# 9xVoice_MikeB_NoRS232_SMD_v1_0d.net
KiCad netlist of a schematic drawn in EAGLE
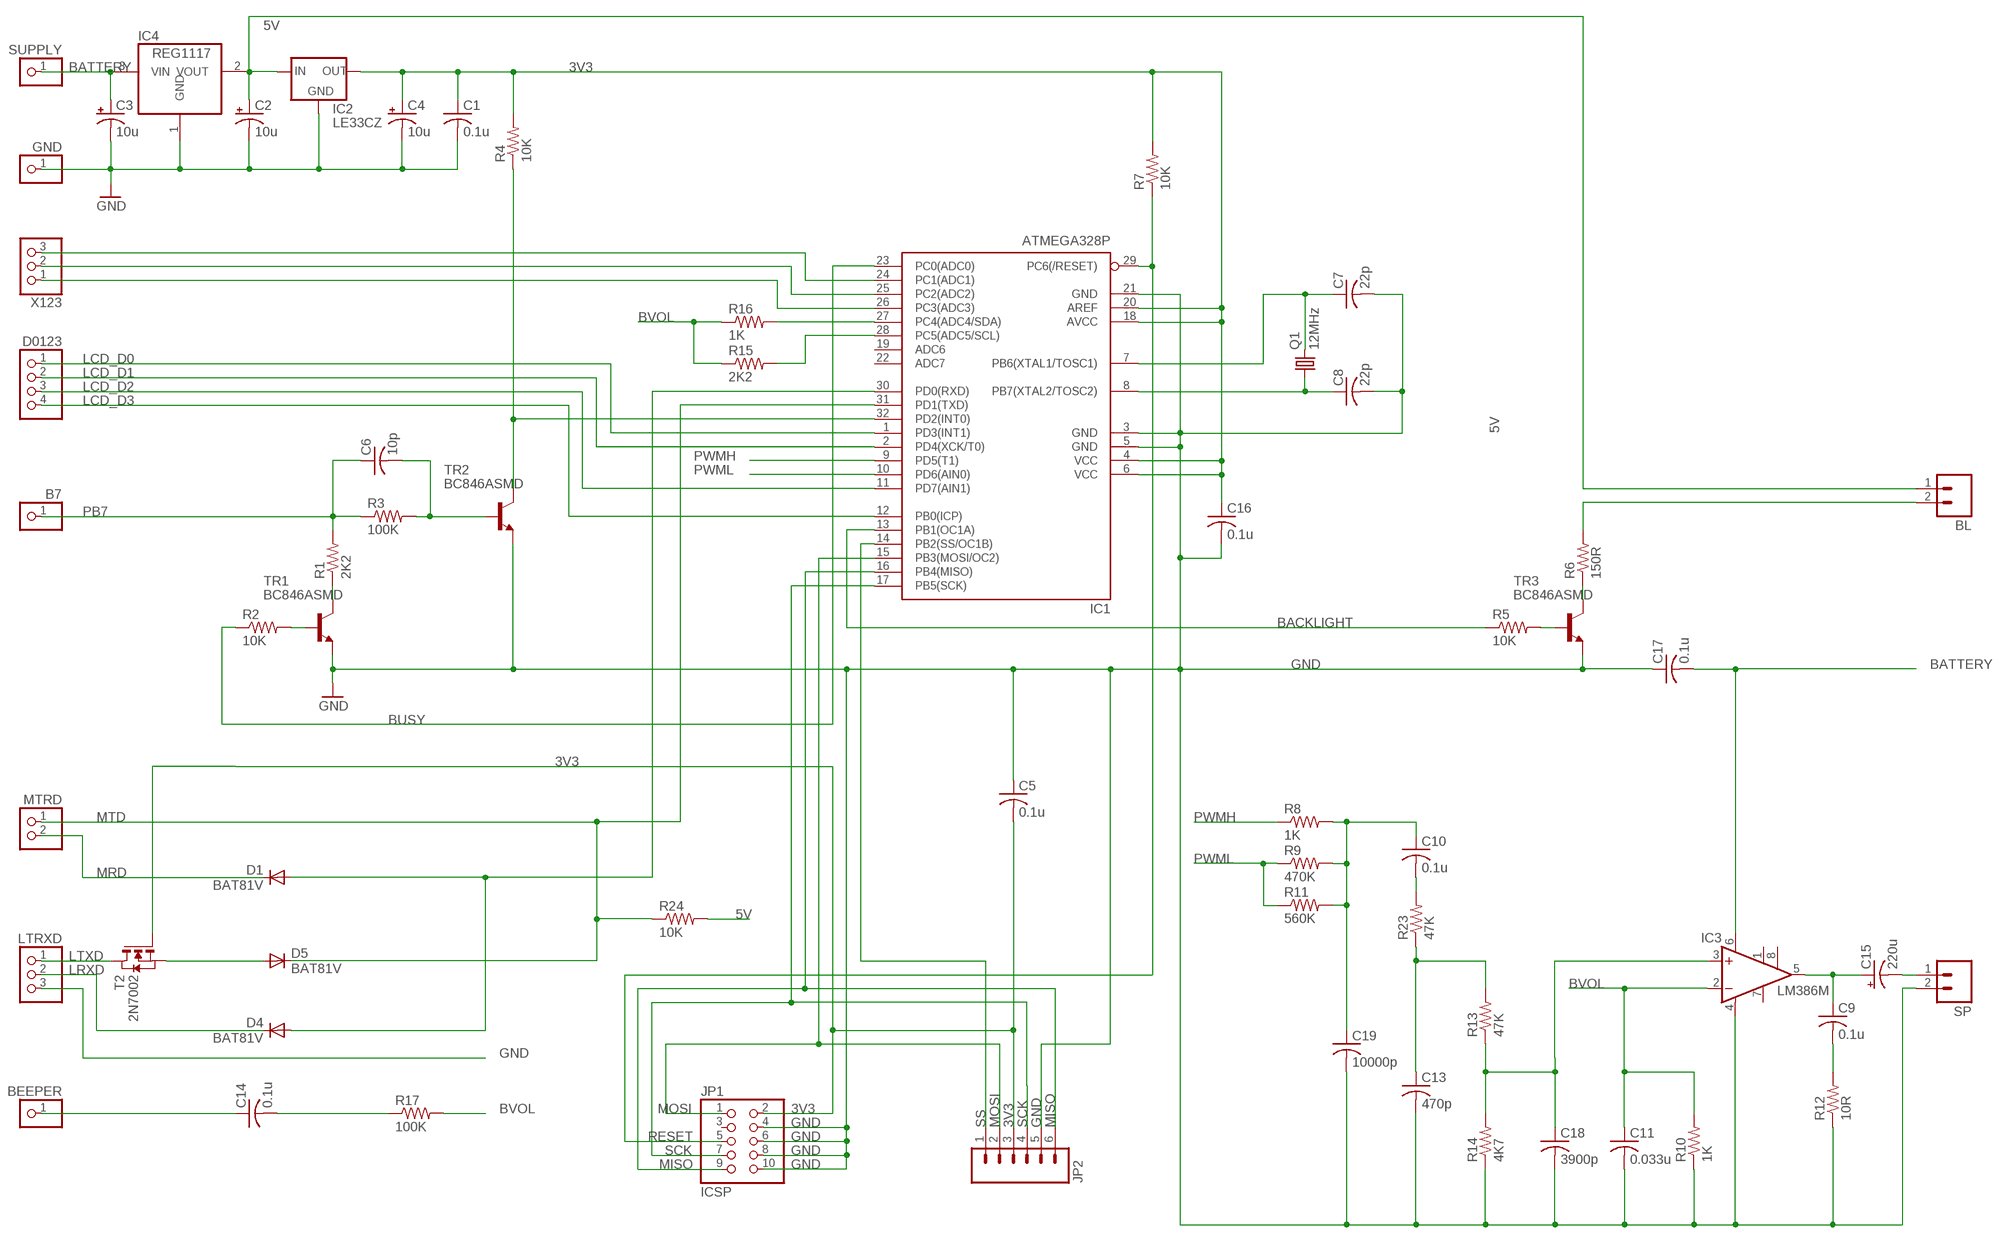
[diagram p0: schematic, sheet 1]

(export (version "E")
  (design (tool "Eeschema 10.0.6"))
  (components
    (comp (ref "B7")
      (value "PINHD-1X1")
      (footprint "eagle-import:1X01")
      (libsource (lib "eagle-import") (part "PINHD-1X1"))
    )
    (comp (ref "BEEPER")
      (value "PINHD-1X1")
      (footprint "eagle-import:1X01")
      (libsource (lib "eagle-import") (part "PINHD-1X1"))
    )
    (comp (ref "BL")
      (value "M02PTH")
      (footprint "eagle-import:1X02")
      (libsource (lib "eagle-import") (part "M02PTH"))
    )
    (comp (ref "C1")
      (value "0.1u")
      (footprint "eagle-import:C1206")
      (libsource (lib "eagle-import") (part "C-USC1206"))
    )
    (comp (ref "C2")
      (value "10u")
      (footprint "eagle-import:A_3216-18R")
      (libsource (lib "eagle-import") (part "CPOL-USA/3216-18R"))
    )
    (comp (ref "C3")
      (value "10u")
      (footprint "eagle-import:A_3216-18R")
      (libsource (lib "eagle-import") (part "CPOL-USA/3216-18R"))
    )
    (comp (ref "C4")
      (value "10u")
      (footprint "eagle-import:A_3216-18R")
      (libsource (lib "eagle-import") (part "CPOL-USA/3216-18R"))
    )
    (comp (ref "C5")
      (value "0.1u")
      (footprint "eagle-import:C1206")
      (libsource (lib "eagle-import") (part "C-USC1206"))
    )
    (comp (ref "C6")
      (value "10p")
      (footprint "eagle-import:C1206")
      (libsource (lib "eagle-import") (part "C-USC1206"))
    )
    (comp (ref "C7")
      (value "22p")
      (footprint "eagle-import:C1206")
      (libsource (lib "eagle-import") (part "C-USC1206"))
    )
    (comp (ref "C8")
      (value "22p")
      (footprint "eagle-import:C1206")
      (libsource (lib "eagle-import") (part "C-USC1206"))
    )
    (comp (ref "C9")
      (value "0.1u")
      (footprint "eagle-import:C1206")
      (libsource (lib "eagle-import") (part "C-USC1206"))
    )
    (comp (ref "C10")
      (value "0.1u")
      (footprint "eagle-import:C1206")
      (libsource (lib "eagle-import") (part "C-USC1206"))
    )
    (comp (ref "C11")
      (value "0.033u")
      (footprint "eagle-import:C1206")
      (libsource (lib "eagle-import") (part "C-USC1206"))
    )
    (comp (ref "C13")
      (value "470p")
      (footprint "eagle-import:C1206")
      (libsource (lib "eagle-import") (part "C-USC1206"))
    )
    (comp (ref "C14")
      (value "0.1u")
      (footprint "eagle-import:C1206")
      (libsource (lib "eagle-import") (part "C-USC1206"))
    )
    (comp (ref "C15")
      (value "220u")
      (footprint "eagle-import:CT7343")
      (libsource (lib "eagle-import") (part "CPOL-USCT7343"))
    )
    (comp (ref "C16")
      (value "0.1u")
      (footprint "eagle-import:C1206")
      (libsource (lib "eagle-import") (part "C-USC1206"))
    )
    (comp (ref "C17")
      (value "0.1u")
      (footprint "eagle-import:C1206")
      (libsource (lib "eagle-import") (part "C-USC1206"))
    )
    (comp (ref "C18")
      (value "3900p")
      (footprint "eagle-import:C1206")
      (libsource (lib "eagle-import") (part "C-USC1206"))
    )
    (comp (ref "C19")
      (value "10000p")
      (footprint "eagle-import:C1206")
      (libsource (lib "eagle-import") (part "C-USC1206"))
    )
    (comp (ref "D1")
      (value "BAT81V")
      (footprint "eagle-import:SOD123")
      (libsource (lib "eagle-import") (part "DIODE-SOD123"))
    )
    (comp (ref "D4")
      (value "BAT81V")
      (footprint "eagle-import:SOD123")
      (libsource (lib "eagle-import") (part "DIODE-SOD123"))
    )
    (comp (ref "D5")
      (value "BAT81V")
      (footprint "eagle-import:SOD123")
      (libsource (lib "eagle-import") (part "DIODE-SOD123"))
    )
    (comp (ref "D0123")
      (value "PINHD-1X4")
      (footprint "eagle-import:1X04")
      (libsource (lib "eagle-import") (part "PINHD-1X4"))
    )
    (comp (ref "GND")
      (value "PINHD-1X1")
      (footprint "eagle-import:1X01")
      (libsource (lib "eagle-import") (part "PINHD-1X1"))
    )
    (comp (ref "IC1")
      (value "ATMEGA328P")
      (footprint "eagle-import:TQFP32-08")
      (fields
        (field (name "MPN") "ATMEGA8-16AU")
        (field (name "MPN_1") "ATMEGA8-16AU")
        (field (name "OC_FARNELL") "9171371")
        (field (name "OC_NEWARK") "73M8863")
      )
      (libsource (lib "eagle-import") (part "MEGA8-AI"))
    )
    (comp (ref "IC2")
      (value "LE33CZ")
      (footprint "eagle-import:SOT23")
      (libsource (lib "eagle-import") (part "XC63FPM"))
    )
    (comp (ref "IC3")
      (value "LM386M")
      (footprint "eagle-import:SO08")
      (libsource (lib "eagle-import") (part "LM386?-M1"))
    )
    (comp (ref "IC4")
      (value "REG1117")
      (footprint "eagle-import:SOT223")
      (libsource (lib "eagle-import") (part "REG1117"))
    )
    (comp (ref "JP1")
      (value "ICSP")
      (footprint "eagle-import:2X05")
      (libsource (lib "eagle-import") (part "PINHD-2X5"))
    )
    (comp (ref "JP2")
      (value "M06SIP")
      (footprint "eagle-import:1X06")
      (libsource (lib "eagle-import") (part "M06SIP"))
    )
    (comp (ref "LTRXD")
      (value "PINHD-1X3")
      (footprint "eagle-import:1X03")
      (libsource (lib "eagle-import") (part "PINHD-1X3"))
    )
    (comp (ref "MTRD")
      (value "PINHD-1X2")
      (footprint "eagle-import:1X02")
      (libsource (lib "eagle-import") (part "PINHD-1X2"))
    )
    (comp (ref "Q1")
      (value "12MHz")
      (footprint "eagle-import:2-SMD")
      (libsource (lib "eagle-import") (part "7A"))
    )
    (comp (ref "R1")
      (value "2K2")
      (footprint "eagle-import:R1206")
      (libsource (lib "eagle-import") (part "R-US_R1206"))
    )
    (comp (ref "R2")
      (value "10K")
      (footprint "eagle-import:R1206")
      (libsource (lib "eagle-import") (part "R-US_R1206"))
    )
    (comp (ref "R3")
      (value "100K")
      (footprint "eagle-import:R1206")
      (libsource (lib "eagle-import") (part "R-US_R1206"))
    )
    (comp (ref "R4")
      (value "10K")
      (footprint "eagle-import:R1206")
      (libsource (lib "eagle-import") (part "R-US_R1206"))
    )
    (comp (ref "R5")
      (value "10K")
      (footprint "eagle-import:R1206")
      (libsource (lib "eagle-import") (part "R-US_R1206"))
    )
    (comp (ref "R6")
      (value "150R")
      (footprint "eagle-import:R1206")
      (libsource (lib "eagle-import") (part "R-US_R1206"))
    )
    (comp (ref "R7")
      (value "10K")
      (footprint "eagle-import:R1206")
      (libsource (lib "eagle-import") (part "R-US_R1206"))
    )
    (comp (ref "R8")
      (value "1K")
      (footprint "eagle-import:R1206")
      (libsource (lib "eagle-import") (part "R-US_R1206"))
    )
    (comp (ref "R9")
      (value "470K")
      (footprint "eagle-import:R1206")
      (libsource (lib "eagle-import") (part "R-US_R1206"))
    )
    (comp (ref "R10")
      (value "1K")
      (footprint "eagle-import:R1206")
      (libsource (lib "eagle-import") (part "R-US_R1206"))
    )
    (comp (ref "R11")
      (value "560K")
      (footprint "eagle-import:R1206")
      (libsource (lib "eagle-import") (part "R-US_R1206"))
    )
    (comp (ref "R12")
      (value "10R")
      (footprint "eagle-import:R1206")
      (libsource (lib "eagle-import") (part "R-US_R1206"))
    )
    (comp (ref "R13")
      (value "47K")
      (footprint "eagle-import:R1206")
      (libsource (lib "eagle-import") (part "R-US_R1206"))
    )
    (comp (ref "R14")
      (value "4K7")
      (footprint "eagle-import:R1206")
      (libsource (lib "eagle-import") (part "R-US_R1206"))
    )
    (comp (ref "R15")
      (value "2K2")
      (footprint "eagle-import:R1206")
      (libsource (lib "eagle-import") (part "R-US_R1206"))
    )
    (comp (ref "R16")
      (value "1K")
      (footprint "eagle-import:R1206")
      (libsource (lib "eagle-import") (part "R-US_R1206"))
    )
    (comp (ref "R17")
      (value "100K")
      (footprint "eagle-import:R1206")
      (libsource (lib "eagle-import") (part "R-US_R1206"))
    )
    (comp (ref "R23")
      (value "47K")
      (footprint "eagle-import:R1206")
      (libsource (lib "eagle-import") (part "R-US_R1206"))
    )
    (comp (ref "R24")
      (value "10K")
      (footprint "eagle-import:R1206")
      (libsource (lib "eagle-import") (part "R-US_R1206"))
    )
    (comp (ref "SP")
      (value "M02PTH")
      (footprint "eagle-import:1X02")
      (libsource (lib "eagle-import") (part "M02PTH"))
    )
    (comp (ref "SUPPLY")
      (value "PINHD-1X1")
      (footprint "eagle-import:1X01")
      (libsource (lib "eagle-import") (part "PINHD-1X1"))
    )
    (comp (ref "T2")
      (value "2N7002")
      (footprint "eagle-import:SOT-23")
      (libsource (lib "eagle-import") (part "NMOSSOT23"))
    )
    (comp (ref "TR1")
      (value "BC846ASMD")
      (footprint "eagle-import:SOT23")
      (libsource (lib "eagle-import") (part "BC846SMDA"))
    )
    (comp (ref "TR2")
      (value "BC846ASMD")
      (footprint "eagle-import:SOT23")
      (libsource (lib "eagle-import") (part "BC846SMDA"))
    )
    (comp (ref "TR3")
      (value "BC846ASMD")
      (footprint "eagle-import:SOT23")
      (libsource (lib "eagle-import") (part "BC846SMDA"))
    )
    (comp (ref "X123")
      (value "PINHD-1X3")
      (footprint "eagle-import:1X03")
      (libsource (lib "eagle-import") (part "PINHD-1X3"))
    )
  )
  (nets
    (net (code "1") (name "/3V3") (class "Default")
      (node (ref "C1") (pin "1") (pinfunction "1_1") (pintype "passive"))
      (node (ref "C16") (pin "1") (pinfunction "1_1") (pintype "passive"))
      (node (ref "C4") (pin "+") (pinfunction "+_+") (pintype "passive"))
      (node (ref "C5") (pin "2") (pinfunction "2_2") (pintype "passive"))
      (node (ref "IC1") (pin "18") (pinfunction "AVCC_18") (pintype "power_in"))
      (node (ref "IC1") (pin "20") (pinfunction "AREF_20") (pintype "passive"))
      (node (ref "IC1") (pin "4") (pinfunction "VCC_4") (pintype "power_in"))
      (node (ref "IC1") (pin "6") (pinfunction "VCC_6") (pintype "power_in"))
      (node (ref "IC2") (pin "2") (pinfunction "OUT_2") (pintype "passive"))
      (node (ref "JP1") (pin "2") (pinfunction "2_2") (pintype "passive"))
      (node (ref "JP2") (pin "3") (pinfunction "3_3") (pintype "passive"))
      (node (ref "R4") (pin "2") (pinfunction "2_2") (pintype "passive"))
      (node (ref "R7") (pin "2") (pinfunction "2_2") (pintype "passive"))
      (node (ref "T2") (pin "3") (pinfunction "G_3") (pintype "passive"))
    )
    (net (code "2") (name "/5V") (class "Default")
      (node (ref "BL") (pin "1") (pinfunction "1_1") (pintype "passive"))
      (node (ref "C2") (pin "+") (pinfunction "+_+") (pintype "passive"))
      (node (ref "IC2") (pin "3") (pinfunction "IN_3") (pintype "input"))
      (node (ref "IC4") (pin "2") (pinfunction "VOUT_2") (pintype "output"))
      (node (ref "R24") (pin "2") (pinfunction "2_2") (pintype "passive"))
    )
    (net (code "3") (name "/BACKLIGHT") (class "Default")
      (node (ref "IC1") (pin "13") (pinfunction "PB1(OC1A)_13") (pintype "bidirectional"))
      (node (ref "R5") (pin "1") (pinfunction "1_1") (pintype "passive"))
    )
    (net (code "4") (name "/BATTERY") (class "Default")
      (node (ref "C17") (pin "2") (pinfunction "2_2") (pintype "passive"))
      (node (ref "C3") (pin "+") (pinfunction "+_+") (pintype "passive"))
      (node (ref "IC3") (pin "6") (pinfunction "VS_6") (pintype "power_in"))
      (node (ref "IC4") (pin "3") (pinfunction "VIN_3") (pintype "input"))
      (node (ref "SUPPLY") (pin "1") (pinfunction "1_1") (pintype "passive"))
    )
    (net (code "5") (name "/BUSY") (class "Default")
      (node (ref "IC1") (pin "23") (pinfunction "PC0(ADC0)_23") (pintype "bidirectional"))
      (node (ref "R2") (pin "1") (pinfunction "1_1") (pintype "passive"))
    )
    (net (code "6") (name "/BVOL") (class "Default")
      (node (ref "C11") (pin "1") (pinfunction "1_1") (pintype "passive"))
      (node (ref "IC3") (pin "2") (pinfunction "-IN_2") (pintype "input"))
      (node (ref "R10") (pin "2") (pinfunction "2_2") (pintype "passive"))
      (node (ref "R15") (pin "1") (pinfunction "1_1") (pintype "passive"))
      (node (ref "R16") (pin "1") (pinfunction "1_1") (pintype "passive"))
      (node (ref "R17") (pin "2") (pinfunction "2_2") (pintype "passive"))
    )
    (net (code "7") (name "/LCD_D0") (class "Default")
      (node (ref "D0123") (pin "1") (pinfunction "1_1") (pintype "passive"))
      (node (ref "IC1") (pin "1") (pinfunction "PD3(INT1)_1") (pintype "bidirectional"))
    )
    (net (code "8") (name "/LCD_D1") (class "Default")
      (node (ref "D0123") (pin "2") (pinfunction "2_2") (pintype "passive"))
      (node (ref "IC1") (pin "2") (pinfunction "PD4(XCK/T0)_2") (pintype "bidirectional"))
    )
    (net (code "9") (name "/LCD_D2") (class "Default")
      (node (ref "D0123") (pin "3") (pinfunction "3_3") (pintype "passive"))
      (node (ref "IC1") (pin "11") (pinfunction "PD7(AIN1)_11") (pintype "bidirectional"))
    )
    (net (code "10") (name "/LCD_D3") (class "Default")
      (node (ref "D0123") (pin "4") (pinfunction "4_4") (pintype "passive"))
      (node (ref "IC1") (pin "12") (pinfunction "PB0(ICP)_12") (pintype "bidirectional"))
    )
    (net (code "11") (name "/LRXD") (class "Default")
      (node (ref "D4") (pin "C") (pinfunction "C_C") (pintype "passive"))
      (node (ref "LTRXD") (pin "2") (pinfunction "2_2") (pintype "passive"))
    )
    (net (code "12") (name "/LTXD") (class "Default")
      (node (ref "LTRXD") (pin "1") (pinfunction "1_1") (pintype "passive"))
      (node (ref "T2") (pin "1") (pinfunction "D_1") (pintype "passive"))
    )
    (net (code "13") (name "/MISO") (class "Default")
      (node (ref "IC1") (pin "16") (pinfunction "PB4(MISO)_16") (pintype "bidirectional"))
      (node (ref "JP1") (pin "9") (pinfunction "9_9") (pintype "passive"))
      (node (ref "JP2") (pin "6") (pinfunction "6_6") (pintype "passive"))
    )
    (net (code "14") (name "/MOSI") (class "Default")
      (node (ref "IC1") (pin "15") (pinfunction "PB3(MOSI/OC2)_15") (pintype "bidirectional"))
      (node (ref "JP1") (pin "1") (pinfunction "1_1") (pintype "passive"))
      (node (ref "JP2") (pin "2") (pinfunction "2_2") (pintype "passive"))
    )
    (net (code "15") (name "/MRD") (class "Default")
      (node (ref "D1") (pin "C") (pinfunction "C_C") (pintype "passive"))
      (node (ref "MTRD") (pin "2") (pinfunction "2_2") (pintype "passive"))
    )
    (net (code "16") (name "/MTD") (class "Default")
      (node (ref "D5") (pin "C") (pinfunction "C_C") (pintype "passive"))
      (node (ref "IC1") (pin "31") (pinfunction "PD1(TXD)_31") (pintype "bidirectional"))
      (node (ref "MTRD") (pin "1") (pinfunction "1_1") (pintype "passive"))
      (node (ref "R24") (pin "1") (pinfunction "1_1") (pintype "passive"))
    )
    (net (code "17") (name "/PB7") (class "Default")
      (node (ref "B7") (pin "1") (pinfunction "1_1") (pintype "passive"))
      (node (ref "C6") (pin "1") (pinfunction "1_1") (pintype "passive"))
      (node (ref "R1") (pin "2") (pinfunction "2_2") (pintype "passive"))
      (node (ref "R3") (pin "1") (pinfunction "1_1") (pintype "passive"))
    )
    (net (code "18") (name "/PWMH") (class "Default")
      (node (ref "IC1") (pin "9") (pinfunction "PD5(T1)_9") (pintype "bidirectional"))
      (node (ref "R8") (pin "1") (pinfunction "1_1") (pintype "passive"))
    )
    (net (code "19") (name "/PWML") (class "Default")
      (node (ref "IC1") (pin "10") (pinfunction "PD6(AIN0)_10") (pintype "bidirectional"))
      (node (ref "R11") (pin "1") (pinfunction "1_1") (pintype "passive"))
      (node (ref "R9") (pin "1") (pinfunction "1_1") (pintype "passive"))
    )
    (net (code "20") (name "/RESET") (class "Default")
      (node (ref "IC1") (pin "29") (pinfunction "PC6(/RESET)_29") (pintype "bidirectional"))
      (node (ref "JP1") (pin "5") (pinfunction "5_5") (pintype "passive"))
      (node (ref "R7") (pin "1") (pinfunction "1_1") (pintype "passive"))
    )
    (net (code "21") (name "/SCK") (class "Default")
      (node (ref "IC1") (pin "17") (pinfunction "PB5(SCK)_17") (pintype "bidirectional"))
      (node (ref "JP1") (pin "7") (pinfunction "7_7") (pintype "passive"))
      (node (ref "JP2") (pin "4") (pinfunction "4_4") (pintype "passive"))
    )
    (net (code "22") (name "/SS") (class "Default")
      (node (ref "IC1") (pin "14") (pinfunction "PB2(SS/OC1B)_14") (pintype "bidirectional"))
      (node (ref "JP2") (pin "1") (pinfunction "1_1") (pintype "passive"))
    )
    (net (code "23") (name "GND") (class "Default")
      (node (ref "C1") (pin "2") (pinfunction "2_2") (pintype "passive"))
      (node (ref "C11") (pin "2") (pinfunction "2_2") (pintype "passive"))
      (node (ref "C13") (pin "2") (pinfunction "2_2") (pintype "passive"))
      (node (ref "C16") (pin "2") (pinfunction "2_2") (pintype "passive"))
      (node (ref "C17") (pin "1") (pinfunction "1_1") (pintype "passive"))
      (node (ref "C18") (pin "2") (pinfunction "2_2") (pintype "passive"))
      (node (ref "C19") (pin "2") (pinfunction "2_2") (pintype "passive"))
      (node (ref "C2") (pin "-") (pinfunction "-_-") (pintype "passive"))
      (node (ref "C3") (pin "-") (pinfunction "-_-") (pintype "passive"))
      (node (ref "C4") (pin "-") (pinfunction "-_-") (pintype "passive"))
      (node (ref "C5") (pin "1") (pinfunction "1_1") (pintype "passive"))
      (node (ref "C7") (pin "2") (pinfunction "2_2") (pintype "passive"))
      (node (ref "C8") (pin "2") (pinfunction "2_2") (pintype "passive"))
      (node (ref "GND") (pin "1") (pinfunction "1_1") (pintype "passive"))
      (node (ref "IC1") (pin "21") (pinfunction "GND_21") (pintype "power_in"))
      (node (ref "IC1") (pin "3") (pinfunction "GND_3") (pintype "power_in"))
      (node (ref "IC1") (pin "5") (pinfunction "GND_5") (pintype "power_in"))
      (node (ref "IC2") (pin "1") (pinfunction "GND_1") (pintype "input"))
      (node (ref "IC3") (pin "4") (pinfunction "GND_4") (pintype "power_in"))
      (node (ref "IC4") (pin "1") (pinfunction "GND_1") (pintype "power_in"))
      (node (ref "JP1") (pin "10") (pinfunction "10_10") (pintype "passive"))
      (node (ref "JP1") (pin "4") (pinfunction "4_4") (pintype "passive"))
      (node (ref "JP1") (pin "6") (pinfunction "6_6") (pintype "passive"))
      (node (ref "JP1") (pin "8") (pinfunction "8_8") (pintype "passive"))
      (node (ref "JP2") (pin "5") (pinfunction "5_5") (pintype "passive"))
      (node (ref "LTRXD") (pin "3") (pinfunction "3_3") (pintype "passive"))
      (node (ref "R10") (pin "1") (pinfunction "1_1") (pintype "passive"))
      (node (ref "R12") (pin "1") (pinfunction "1_1") (pintype "passive"))
      (node (ref "R14") (pin "1") (pinfunction "1_1") (pintype "passive"))
      (node (ref "SP") (pin "2") (pinfunction "2_2") (pintype "passive"))
      (node (ref "TR1") (pin "2") (pinfunction "E_2") (pintype "passive"))
      (node (ref "TR2") (pin "2") (pinfunction "E_2") (pintype "passive"))
      (node (ref "TR3") (pin "2") (pinfunction "E_2") (pintype "passive"))
    )
    (net (code "24") (name "Net-(BEEPER-Pad1)") (class "Default")
      (node (ref "BEEPER") (pin "1") (pinfunction "1_1") (pintype "passive"))
      (node (ref "C14") (pin "1") (pinfunction "1_1") (pintype "passive"))
    )
    (net (code "25") (name "Net-(BL-Pad2)") (class "Default")
      (node (ref "BL") (pin "2") (pinfunction "2_2") (pintype "passive"))
      (node (ref "R6") (pin "2") (pinfunction "2_2") (pintype "passive"))
    )
    (net (code "26") (name "Net-(C9-Pad2)") (class "Default")
      (node (ref "C9") (pin "2") (pinfunction "2_2") (pintype "passive"))
      (node (ref "R12") (pin "2") (pinfunction "2_2") (pintype "passive"))
    )
    (net (code "27") (name "Net-(C10-Pad1)") (class "Default")
      (node (ref "C10") (pin "1") (pinfunction "1_1") (pintype "passive"))
      (node (ref "C19") (pin "1") (pinfunction "1_1") (pintype "passive"))
      (node (ref "R11") (pin "2") (pinfunction "2_2") (pintype "passive"))
      (node (ref "R8") (pin "2") (pinfunction "2_2") (pintype "passive"))
      (node (ref "R9") (pin "2") (pinfunction "2_2") (pintype "passive"))
    )
    (net (code "28") (name "Net-(C10-Pad2)") (class "Default")
      (node (ref "C10") (pin "2") (pinfunction "2_2") (pintype "passive"))
      (node (ref "R23") (pin "2") (pinfunction "2_2") (pintype "passive"))
    )
    (net (code "29") (name "Net-(C13-Pad1)") (class "Default")
      (node (ref "C13") (pin "1") (pinfunction "1_1") (pintype "passive"))
      (node (ref "R13") (pin "2") (pinfunction "2_2") (pintype "passive"))
      (node (ref "R23") (pin "1") (pinfunction "1_1") (pintype "passive"))
    )
    (net (code "30") (name "Net-(C14-Pad2)") (class "Default")
      (node (ref "C14") (pin "2") (pinfunction "2_2") (pintype "passive"))
      (node (ref "R17") (pin "1") (pinfunction "1_1") (pintype "passive"))
    )
    (net (code "31") (name "Net-(C15-Pad-)") (class "Default")
      (node (ref "C15") (pin "-") (pinfunction "-_-") (pintype "passive"))
      (node (ref "SP") (pin "1") (pinfunction "1_1") (pintype "passive"))
    )
    (net (code "32") (name "Net-(IC1-PB6(XTAL1{slash}TOSC1))") (class "Default")
      (node (ref "C7") (pin "1") (pinfunction "1_1") (pintype "passive"))
      (node (ref "IC1") (pin "7") (pinfunction "PB6(XTAL1/TOSC1)_7") (pintype "bidirectional"))
      (node (ref "Q1") (pin "P$2") (pinfunction "2_P$2") (pintype "passive"))
    )
    (net (code "33") (name "Net-(IC1-PB7(XTAL2{slash}TOSC2))") (class "Default")
      (node (ref "C8") (pin "1") (pinfunction "1_1") (pintype "passive"))
      (node (ref "IC1") (pin "8") (pinfunction "PB7(XTAL2/TOSC2)_8") (pintype "bidirectional"))
      (node (ref "Q1") (pin "P$1") (pinfunction "1_P$1") (pintype "passive"))
    )
    (net (code "34") (name "Net-(IC1-PC1(ADC1))") (class "Default")
      (node (ref "IC1") (pin "24") (pinfunction "PC1(ADC1)_24") (pintype "bidirectional"))
      (node (ref "X123") (pin "3") (pinfunction "3_3") (pintype "passive"))
    )
    (net (code "35") (name "Net-(IC1-PC2(ADC2))") (class "Default")
      (node (ref "IC1") (pin "25") (pinfunction "PC2(ADC2)_25") (pintype "bidirectional"))
      (node (ref "X123") (pin "2") (pinfunction "2_2") (pintype "passive"))
    )
    (net (code "36") (name "Net-(IC1-PC3(ADC3))") (class "Default")
      (node (ref "IC1") (pin "26") (pinfunction "PC3(ADC3)_26") (pintype "bidirectional"))
      (node (ref "X123") (pin "1") (pinfunction "1_1") (pintype "passive"))
    )
    (net (code "37") (name "Net-(IC1-PC4(ADC4{slash}SDA))") (class "Default")
      (node (ref "IC1") (pin "27") (pinfunction "PC4(ADC4/SDA)_27") (pintype "bidirectional"))
      (node (ref "R16") (pin "2") (pinfunction "2_2") (pintype "passive"))
    )
    (net (code "38") (name "Net-(IC1-PC5(ADC5{slash}SCL))") (class "Default")
      (node (ref "IC1") (pin "28") (pinfunction "PC5(ADC5/SCL)_28") (pintype "bidirectional"))
      (node (ref "R15") (pin "2") (pinfunction "2_2") (pintype "passive"))
    )
    (net (code "39") (name "Net-(IC1-PD0(RXD))") (class "Default")
      (node (ref "D1") (pin "A") (pinfunction "A_A") (pintype "passive"))
      (node (ref "D4") (pin "A") (pinfunction "A_A") (pintype "passive"))
      (node (ref "IC1") (pin "30") (pinfunction "PD0(RXD)_30") (pintype "bidirectional"))
    )
    (net (code "40") (name "Net-(IC1-PD2(INT0))") (class "Default")
      (node (ref "IC1") (pin "32") (pinfunction "PD2(INT0)_32") (pintype "bidirectional"))
      (node (ref "R4") (pin "1") (pinfunction "1_1") (pintype "passive"))
      (node (ref "TR2") (pin "3") (pinfunction "C_3") (pintype "passive"))
    )
    (net (code "41") (name "Net-(IC3-+IN)") (class "Default")
      (node (ref "C18") (pin "1") (pinfunction "1_1") (pintype "passive"))
      (node (ref "IC3") (pin "3") (pinfunction "+IN_3") (pintype "input"))
      (node (ref "R13") (pin "1") (pinfunction "1_1") (pintype "passive"))
      (node (ref "R14") (pin "2") (pinfunction "2_2") (pintype "passive"))
    )
    (net (code "42") (name "Net-(IC3-OUT)") (class "Default")
      (node (ref "C15") (pin "+") (pinfunction "+_+") (pintype "passive"))
      (node (ref "C9") (pin "1") (pinfunction "1_1") (pintype "passive"))
      (node (ref "IC3") (pin "5") (pinfunction "OUT_5") (pintype "output"))
    )
    (net (code "43") (name "Net-(T2-S)") (class "Default")
      (node (ref "D5") (pin "A") (pinfunction "A_A") (pintype "passive"))
      (node (ref "T2") (pin "2") (pinfunction "S_2") (pintype "passive"))
    )
    (net (code "44") (name "Net-(TR1-B)") (class "Default")
      (node (ref "R2") (pin "2") (pinfunction "2_2") (pintype "passive"))
      (node (ref "TR1") (pin "1") (pinfunction "B_1") (pintype "passive"))
    )
    (net (code "45") (name "Net-(TR1-C)") (class "Default")
      (node (ref "R1") (pin "1") (pinfunction "1_1") (pintype "passive"))
      (node (ref "TR1") (pin "3") (pinfunction "C_3") (pintype "passive"))
    )
    (net (code "46") (name "Net-(TR2-B)") (class "Default")
      (node (ref "C6") (pin "2") (pinfunction "2_2") (pintype "passive"))
      (node (ref "R3") (pin "2") (pinfunction "2_2") (pintype "passive"))
      (node (ref "TR2") (pin "1") (pinfunction "B_1") (pintype "passive"))
    )
    (net (code "47") (name "Net-(TR3-B)") (class "Default")
      (node (ref "R5") (pin "2") (pinfunction "2_2") (pintype "passive"))
      (node (ref "TR3") (pin "1") (pinfunction "B_1") (pintype "passive"))
    )
    (net (code "48") (name "Net-(TR3-C)") (class "Default")
      (node (ref "R6") (pin "1") (pinfunction "1_1") (pintype "passive"))
      (node (ref "TR3") (pin "3") (pinfunction "C_3") (pintype "passive"))
    )
    (net (code "49") (name "unconnected-(IC1-ADC6-Pad19)") (class "Default")
      (node (ref "IC1") (pin "19") (pinfunction "ADC6_19") (pintype "bidirectional"))
    )
    (net (code "50") (name "unconnected-(IC1-ADC7-Pad22)") (class "Default")
      (node (ref "IC1") (pin "22") (pinfunction "ADC7_22") (pintype "bidirectional"))
    )
    (net (code "51") (name "unconnected-(IC3-BYPASS-Pad7)") (class "Default")
      (node (ref "IC3") (pin "7") (pinfunction "BYPASS_7") (pintype "passive"))
    )
    (net (code "52") (name "unconnected-(IC3-GAIN-Pad1)") (class "Default")
      (node (ref "IC3") (pin "1") (pinfunction "GAIN_1") (pintype "passive"))
    )
    (net (code "53") (name "unconnected-(IC3-GAIN-Pad8)") (class "Default")
      (node (ref "IC3") (pin "8") (pinfunction "GAIN_8") (pintype "passive"))
    )
    (net (code "54") (name "unconnected-(JP1-Pad3)") (class "Default")
      (node (ref "JP1") (pin "3") (pinfunction "3_3") (pintype "passive"))
    )
  )
)
